# AIM2_-_ADCS_Multiplexing_REVB.net
KiCad netlist of a schematic drawn in Altium Designer
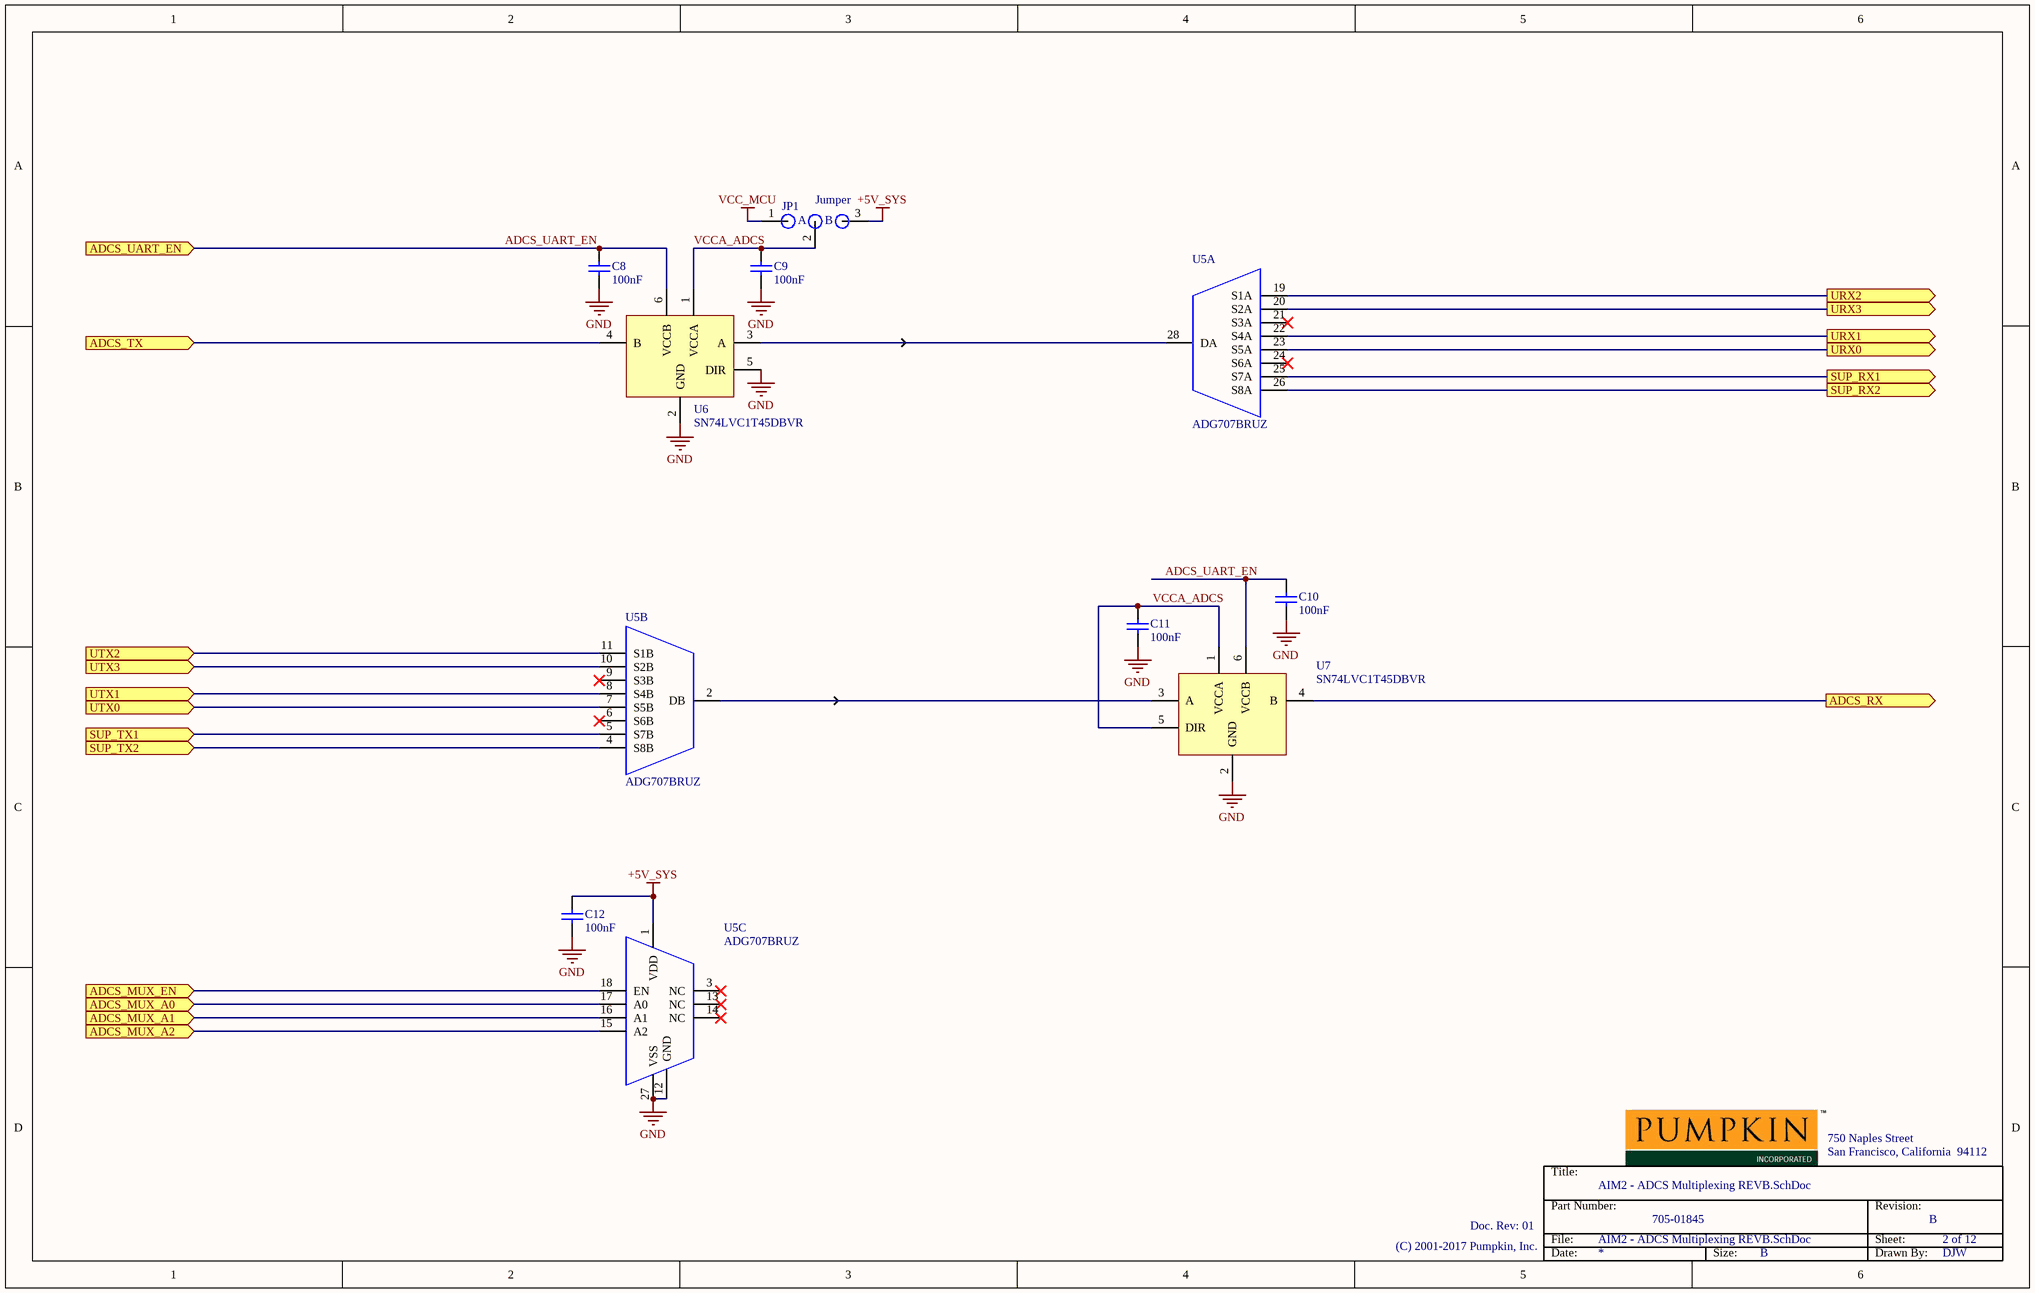
[diagram p0: AIM2 - ADCS Multiplexing REVB.SchDoc]

(export (version "E")
  (design (tool "Eeschema 10.0.6"))
  (components
    (comp (ref "C8")
      (value "100nF")
      (footprint "0603 CAP")
      (description "Capacitor 100nF 0603 X7R 50V 5%")
      (libsource (lib "Supernova passives") (part "Capacitor 100nF 0603"))
    )
    (comp (ref "C9")
      (value "100nF")
      (footprint "0603 CAP")
      (description "Capacitor 100nF 0603 X7R 50V 5%")
      (libsource (lib "Supernova passives") (part "Capacitor 100nF 0603"))
    )
    (comp (ref "C10")
      (value "100nF")
      (footprint "0603 CAP")
      (description "Capacitor 100nF 0603 X7R 50V 5%")
      (libsource (lib "Supernova passives") (part "Capacitor 100nF 0603"))
    )
    (comp (ref "C11")
      (value "100nF")
      (footprint "0603 CAP")
      (description "Capacitor 100nF 0603 X7R 50V 5%")
      (libsource (lib "Supernova passives") (part "Capacitor 100nF 0603"))
    )
    (comp (ref "C12")
      (value "100nF")
      (footprint "0603 CAP")
      (description "Capacitor 100nF 0603 X7R 50V 5%")
      (libsource (lib "Supernova passives") (part "Capacitor 100nF 0603"))
    )
    (comp (ref "JP1")
      (value "Jumper")
      (footprint "0805 RES 2 way jumper - 1")
      (description "Jumper 0805 2 pos")
      (libsource (lib "Supernova passives") (part "Jumper 2 way 0805"))
    )
    (comp (ref "U5")
      (value "ADG707BRUZ")
      (footprint "28-TSSOP")
      (description "IC Multiplexer 2x 8:1")
      (libsource (lib "Supernova") (part "ADG707BRUZ"))
    )
    (comp (ref "U6")
      (value "SN74LVC1T45DBVR")
      (footprint "SOT23-6")
      (description "IC Logic Isolator 1 channel")
      (libsource (lib "Supernova") (part "SN74LVC1T45DBVR"))
    )
    (comp (ref "U7")
      (value "SN74LVC1T45DBVR")
      (footprint "SOT23-6")
      (description "IC Logic Isolator 1 channel")
      (libsource (lib "") (part "SN74LVC1T45DBVR_1"))
    )
  )
  (nets
    (net (code "1") (name "+5V_SYS") (class "Default")
      (node (ref "C12") (pin "2") (pinfunction "2_2") (pintype "passive"))
      (node (ref "JP1") (pin "3") (pinfunction "5_3") (pintype "passive"))
      (node (ref "U5") (pin "1") (pinfunction "VDD_1") (pintype "passive"))
    )
    (net (code "2") (name "/ADCS_MUX_A0") (class "Default")
      (node (ref "U5") (pin "17") (pinfunction "A0_17") (pintype "passive"))
    )
    (net (code "3") (name "/ADCS_MUX_A1") (class "Default")
      (node (ref "U5") (pin "16") (pinfunction "A1_16") (pintype "passive"))
    )
    (net (code "4") (name "/ADCS_MUX_A2") (class "Default")
      (node (ref "U5") (pin "15") (pinfunction "A2_15") (pintype "passive"))
    )
    (net (code "5") (name "/ADCS_MUX_EN") (class "Default")
      (node (ref "U5") (pin "18") (pinfunction "EN_18") (pintype "passive"))
    )
    (net (code "6") (name "/ADCS_RX") (class "Default")
      (node (ref "U7") (pin "4") (pinfunction "B_4") (pintype "passive"))
    )
    (net (code "7") (name "/ADCS_TX") (class "Default")
      (node (ref "U6") (pin "4") (pinfunction "B_4") (pintype "passive"))
    )
    (net (code "8") (name "/ADCS_UART_EN") (class "Default")
      (node (ref "C10") (pin "2") (pinfunction "2_2") (pintype "passive"))
      (node (ref "C8") (pin "2") (pinfunction "2_2") (pintype "passive"))
      (node (ref "U6") (pin "6") (pinfunction "VCCB_6") (pintype "passive"))
      (node (ref "U7") (pin "6") (pinfunction "VCCB_6") (pintype "passive"))
    )
    (net (code "9") (name "/SUP_RX1") (class "Default")
      (node (ref "U5") (pin "25") (pinfunction "S7A_25") (pintype "passive"))
    )
    (net (code "10") (name "/SUP_RX2") (class "Default")
      (node (ref "U5") (pin "26") (pinfunction "S8A_26") (pintype "passive"))
    )
    (net (code "11") (name "/SUP_TX1") (class "Default")
      (node (ref "U5") (pin "5") (pinfunction "S7B_5") (pintype "passive"))
    )
    (net (code "12") (name "/SUP_TX2") (class "Default")
      (node (ref "U5") (pin "4") (pinfunction "S8B_4") (pintype "passive"))
    )
    (net (code "13") (name "/URX0") (class "Default")
      (node (ref "U5") (pin "23") (pinfunction "S5A_23") (pintype "passive"))
    )
    (net (code "14") (name "/URX1") (class "Default")
      (node (ref "U5") (pin "22") (pinfunction "S4A_22") (pintype "passive"))
    )
    (net (code "15") (name "/URX2") (class "Default")
      (node (ref "U5") (pin "19") (pinfunction "S1A_19") (pintype "passive"))
    )
    (net (code "16") (name "/URX3") (class "Default")
      (node (ref "U5") (pin "20") (pinfunction "S2A_20") (pintype "passive"))
    )
    (net (code "17") (name "/UTX0") (class "Default")
      (node (ref "U5") (pin "7") (pinfunction "S5B_7") (pintype "passive"))
    )
    (net (code "18") (name "/UTX1") (class "Default")
      (node (ref "U5") (pin "8") (pinfunction "S4B_8") (pintype "passive"))
    )
    (net (code "19") (name "/UTX2") (class "Default")
      (node (ref "U5") (pin "11") (pinfunction "S1B_11") (pintype "passive"))
    )
    (net (code "20") (name "/UTX3") (class "Default")
      (node (ref "U5") (pin "10") (pinfunction "S2B_10") (pintype "passive"))
    )
    (net (code "21") (name "/VCCA_ADCS") (class "Default")
      (node (ref "C11") (pin "2") (pinfunction "2_2") (pintype "passive"))
      (node (ref "C9") (pin "2") (pinfunction "2_2") (pintype "passive"))
      (node (ref "JP1") (pin "2") (pinfunction "5_2") (pintype "passive"))
      (node (ref "U6") (pin "1") (pinfunction "VCCA_1") (pintype "passive"))
      (node (ref "U7") (pin "1") (pinfunction "VCCA_1") (pintype "passive"))
      (node (ref "U7") (pin "5") (pinfunction "DIR_5") (pintype "passive"))
    )
    (net (code "22") (name "GND") (class "Default")
      (node (ref "C10") (pin "1") (pinfunction "1_1") (pintype "passive"))
      (node (ref "C11") (pin "1") (pinfunction "1_1") (pintype "passive"))
      (node (ref "C12") (pin "1") (pinfunction "1_1") (pintype "passive"))
      (node (ref "C8") (pin "1") (pinfunction "1_1") (pintype "passive"))
      (node (ref "C9") (pin "1") (pinfunction "1_1") (pintype "passive"))
      (node (ref "U5") (pin "12") (pinfunction "GND_12") (pintype "passive"))
      (node (ref "U5") (pin "27") (pinfunction "VSS_27") (pintype "passive"))
      (node (ref "U6") (pin "2") (pinfunction "GND_2") (pintype "passive"))
      (node (ref "U6") (pin "5") (pinfunction "DIR_5") (pintype "passive"))
      (node (ref "U7") (pin "2") (pinfunction "GND_2") (pintype "passive"))
    )
    (net (code "23") (name "Net-(U5A-DA)") (class "Default")
      (node (ref "U5") (pin "28") (pinfunction "DA_28") (pintype "passive"))
      (node (ref "U6") (pin "3") (pinfunction "A_3") (pintype "passive"))
    )
    (net (code "24") (name "Net-(U5B-DB)") (class "Default")
      (node (ref "U5") (pin "2") (pinfunction "DB_2") (pintype "passive"))
      (node (ref "U7") (pin "3") (pinfunction "A_3") (pintype "passive"))
    )
    (net (code "25") (name "VCC_MCU") (class "Default")
      (node (ref "JP1") (pin "1") (pinfunction "5_1") (pintype "passive"))
    )
    (net (code "26") (name "unconnected-(U5A-S3A-Pad21)") (class "Default")
      (node (ref "U5") (pin "21") (pinfunction "S3A_21") (pintype "passive+no_connect"))
    )
    (net (code "27") (name "unconnected-(U5A-S6A-Pad24)") (class "Default")
      (node (ref "U5") (pin "24") (pinfunction "S6A_24") (pintype "passive+no_connect"))
    )
    (net (code "28") (name "unconnected-(U5B-S3B-Pad9)") (class "Default")
      (node (ref "U5") (pin "9") (pinfunction "S3B_9") (pintype "passive+no_connect"))
    )
    (net (code "29") (name "unconnected-(U5B-S6B-Pad6)") (class "Default")
      (node (ref "U5") (pin "6") (pinfunction "S6B_6") (pintype "passive+no_connect"))
    )
    (net (code "30") (name "unconnected-(U5C-NC-Pad3)") (class "Default")
      (node (ref "U5") (pin "3") (pinfunction "NC_3") (pintype "passive+no_connect"))
    )
    (net (code "31") (name "unconnected-(U5C-NC-Pad13)") (class "Default")
      (node (ref "U5") (pin "13") (pinfunction "NC_13") (pintype "passive+no_connect"))
    )
    (net (code "32") (name "unconnected-(U5C-NC-Pad14)") (class "Default")
      (node (ref "U5") (pin "14") (pinfunction "NC_14") (pintype "passive+no_connect"))
    )
  )
)
